# MICHAv41.net
KiCad netlist of a schematic drawn in EAGLE
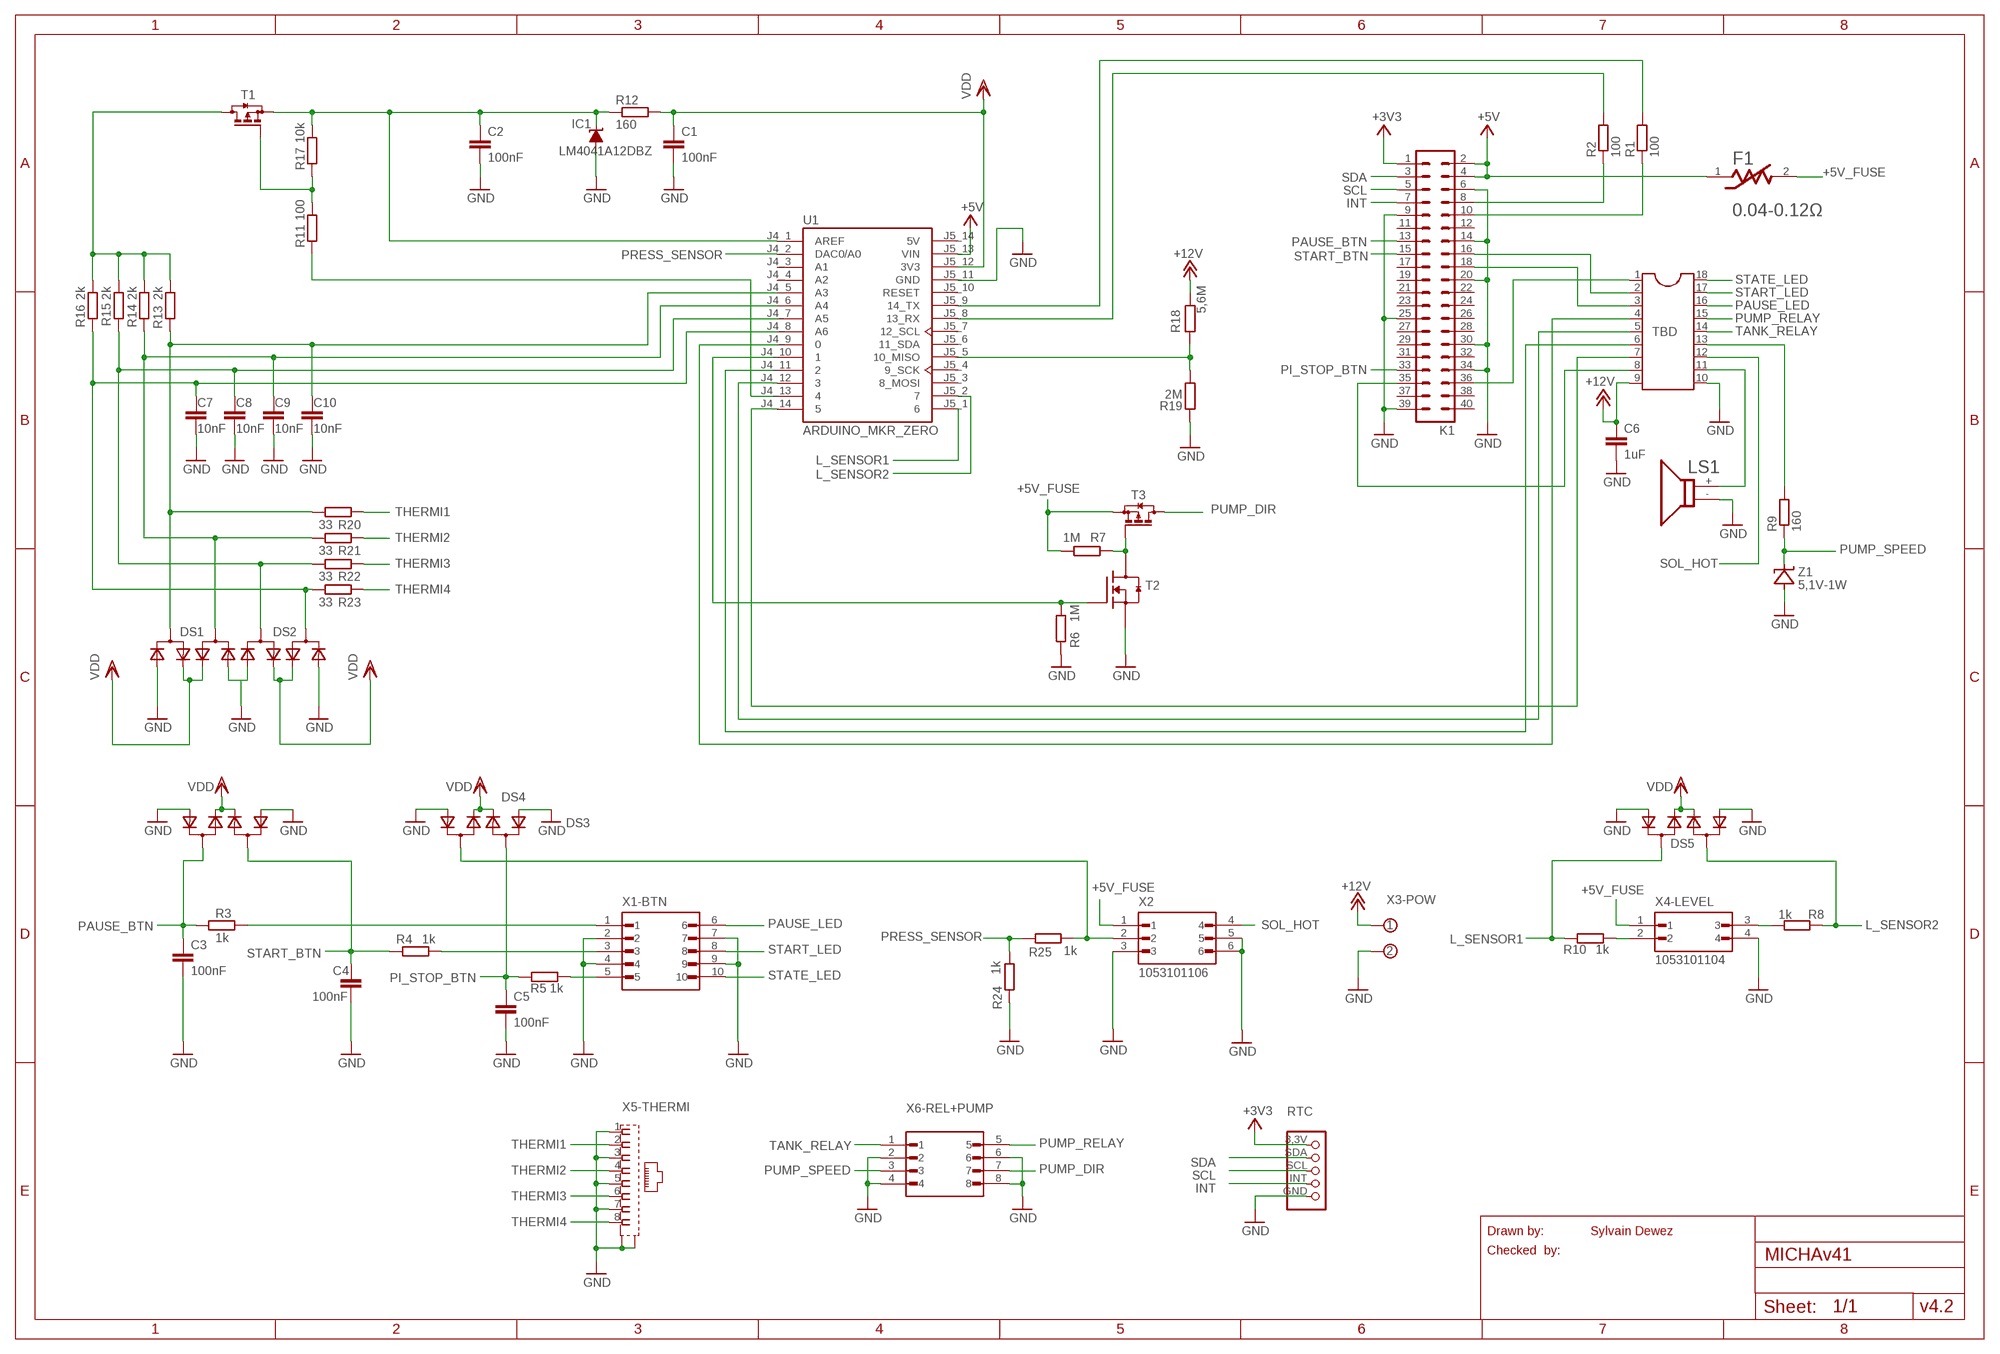
[diagram p0: schematic, sheet 1]

(export (version "E")
  (design (tool "Eeschema 10.0.6"))
  (components
    (comp (ref "C1")
      (value "100nF")
      (footprint "eagle-import:C1206")
      (libsource (lib "eagle-import") (part "C-EUC1206"))
    )
    (comp (ref "C2")
      (value "100nF")
      (footprint "eagle-import:C1206")
      (libsource (lib "eagle-import") (part "C-EUC1206"))
    )
    (comp (ref "C3")
      (value "100nF")
      (footprint "eagle-import:C1206")
      (libsource (lib "eagle-import") (part "C-EUC1206"))
    )
    (comp (ref "C4")
      (value "100nF")
      (footprint "eagle-import:C1206")
      (libsource (lib "eagle-import") (part "C-EUC1206"))
    )
    (comp (ref "C5")
      (value "100nF")
      (footprint "eagle-import:C1206")
      (libsource (lib "eagle-import") (part "C-EUC1206"))
    )
    (comp (ref "C6")
      (value "1uF")
      (footprint "eagle-import:C1206")
      (libsource (lib "eagle-import") (part "C-EUC1206"))
    )
    (comp (ref "C7")
      (value "10nF")
      (footprint "eagle-import:C1206")
      (libsource (lib "eagle-import") (part "C-EUC1206"))
    )
    (comp (ref "C8")
      (value "10nF")
      (footprint "eagle-import:C1206")
      (libsource (lib "eagle-import") (part "C-EUC1206"))
    )
    (comp (ref "C9")
      (value "10nF")
      (footprint "eagle-import:C1206")
      (libsource (lib "eagle-import") (part "C-EUC1206"))
    )
    (comp (ref "C10")
      (value "10nF")
      (footprint "eagle-import:C1206")
      (libsource (lib "eagle-import") (part "C-EUC1206"))
    )
    (comp (ref "DS1")
      (value "CMXSH2-4LSTRPBFREE")
      (footprint "eagle-import:CMXSH2-4LSTRPBFREE")
      (libsource (lib "eagle-import") (part "CMXSH2-4LSTRPBFREE"))
    )
    (comp (ref "DS2")
      (value "CMXSH2-4LSTRPBFREE")
      (footprint "eagle-import:CMXSH2-4LSTRPBFREE")
      (libsource (lib "eagle-import") (part "CMXSH2-4LSTRPBFREE"))
    )
    (comp (ref "DS3")
      (value "CMXSH2-4LSTRPBFREE")
      (footprint "eagle-import:CMXSH2-4LSTRPBFREE")
      (libsource (lib "eagle-import") (part "CMXSH2-4LSTRPBFREE"))
    )
    (comp (ref "DS4")
      (value "CMXSH2-4LSTRPBFREE")
      (footprint "eagle-import:CMXSH2-4LSTRPBFREE")
      (libsource (lib "eagle-import") (part "CMXSH2-4LSTRPBFREE"))
    )
    (comp (ref "DS5")
      (value "CMXSH2-4LSTRPBFREE")
      (footprint "eagle-import:CMXSH2-4LSTRPBFREE")
      (libsource (lib "eagle-import") (part "CMXSH2-4LSTRPBFREE"))
    )
    (comp (ref "F1")
      (value "LITTELFUSE_INC_1206L150THWRLITTELFUSE_INC_1206L150THWR_0_0")
      (footprint "eagle-import:LITTELFUSE_INC_1206L150THWR_0")
      (fields
        (field (name "DIGIKEY_PART_NUMBER") "F3372CT-ND")
        (field (name "MF") "Littelfuse Inc")
        (field (name "MOUSER_PART_NUMBER") "576-1206L150THWR")
      )
      (libsource (lib "eagle-import") (part "LITTELFUSE_INC_1206L150THWRLITTELFUSE_INC_1206L150THWR_0_0"))
    )
    (comp (ref "IC1")
      (value "LM4041A12DBZ")
      (footprint "eagle-import:DBZ_R-PDSO-G3")
      (fields (field (name "MPN") "LM4041A12IDBZR"))
      (libsource (lib "eagle-import") (part "LM4041DBZA12"))
    )
    (comp (ref "K1")
      (value "PIN20X2")
      (footprint "eagle-import:PIN_20X2")
      (libsource (lib "eagle-import") (part "PIN20X2"))
    )
    (comp (ref "LS1")
      (value "RSPRO-BUZZER-7800743")
      (footprint "eagle-import:RSPRO-BUZZER-7800743")
      (libsource (lib "eagle-import") (part "RSPRO-BUZZER-7800743"))
    )
    (comp (ref "R1")
      (value "100")
      (footprint "eagle-import:R1206")
      (libsource (lib "eagle-import") (part "resistor_R-EU_R1206"))
    )
    (comp (ref "R2")
      (value "100")
      (footprint "eagle-import:R1206")
      (libsource (lib "eagle-import") (part "resistor_R-EU_R1206"))
    )
    (comp (ref "R3")
      (value "1k")
      (footprint "eagle-import:R1206")
      (libsource (lib "eagle-import") (part "resistor_R-EU_R1206"))
    )
    (comp (ref "R4")
      (value "1k")
      (footprint "eagle-import:R1206")
      (libsource (lib "eagle-import") (part "resistor_R-EU_R1206"))
    )
    (comp (ref "R5")
      (value "1k")
      (footprint "eagle-import:R1206")
      (libsource (lib "eagle-import") (part "resistor_R-EU_R1206"))
    )
    (comp (ref "R6")
      (value "1M")
      (footprint "eagle-import:R1206")
      (libsource (lib "eagle-import") (part "resistor_R-EU_R1206"))
    )
    (comp (ref "R7")
      (value "1M")
      (footprint "eagle-import:R1206")
      (libsource (lib "eagle-import") (part "resistor_R-EU_R1206"))
    )
    (comp (ref "R8")
      (value "1k")
      (footprint "eagle-import:R1206")
      (libsource (lib "eagle-import") (part "resistor_R-EU_R1206"))
    )
    (comp (ref "R9")
      (value "160")
      (footprint "eagle-import:R1206")
      (libsource (lib "eagle-import") (part "R-EU_R1206"))
    )
    (comp (ref "R10")
      (value "1k")
      (footprint "eagle-import:R1206")
      (libsource (lib "eagle-import") (part "resistor_R-EU_R1206"))
    )
    (comp (ref "R11")
      (value "100")
      (footprint "eagle-import:R1206")
      (libsource (lib "eagle-import") (part "resistor_R-EU_R1206"))
    )
    (comp (ref "R12")
      (value "160")
      (footprint "eagle-import:R1206")
      (libsource (lib "eagle-import") (part "R-EU_R1206"))
    )
    (comp (ref "R13")
      (value "2k")
      (footprint "eagle-import:R1206")
      (libsource (lib "eagle-import") (part "resistor_R-EU_R1206"))
    )
    (comp (ref "R14")
      (value "2k")
      (footprint "eagle-import:R1206")
      (libsource (lib "eagle-import") (part "resistor_R-EU_R1206"))
    )
    (comp (ref "R15")
      (value "2k")
      (footprint "eagle-import:R1206")
      (libsource (lib "eagle-import") (part "resistor_R-EU_R1206"))
    )
    (comp (ref "R16")
      (value "2k")
      (footprint "eagle-import:R1206")
      (libsource (lib "eagle-import") (part "resistor_R-EU_R1206"))
    )
    (comp (ref "R17")
      (value "10k")
      (footprint "eagle-import:R1206")
      (libsource (lib "eagle-import") (part "resistor_R-EU_R1206"))
    )
    (comp (ref "R18")
      (value "5,6M")
      (footprint "eagle-import:R1206")
      (libsource (lib "eagle-import") (part "resistor_R-EU_R1206"))
    )
    (comp (ref "R19")
      (value "2M")
      (footprint "eagle-import:R1206")
      (libsource (lib "eagle-import") (part "resistor_R-EU_R1206"))
    )
    (comp (ref "R20")
      (value "33")
      (footprint "eagle-import:R1206")
      (libsource (lib "eagle-import") (part "resistor_R-EU_R1206"))
    )
    (comp (ref "R21")
      (value "33")
      (footprint "eagle-import:R1206")
      (libsource (lib "eagle-import") (part "resistor_R-EU_R1206"))
    )
    (comp (ref "R22")
      (value "33")
      (footprint "eagle-import:R1206")
      (libsource (lib "eagle-import") (part "resistor_R-EU_R1206"))
    )
    (comp (ref "R23")
      (value "33")
      (footprint "eagle-import:R1206")
      (libsource (lib "eagle-import") (part "resistor_R-EU_R1206"))
    )
    (comp (ref "R24")
      (value "1k")
      (footprint "eagle-import:R1206")
      (libsource (lib "eagle-import") (part "resistor_R-EU_R1206"))
    )
    (comp (ref "R25")
      (value "1k")
      (footprint "eagle-import:R1206")
      (libsource (lib "eagle-import") (part "resistor_R-EU_R1206"))
    )
    (comp (ref "RTC")
      (value "ODROID_C4_RTC_SHIELD")
      (footprint "eagle-import:ODROID_C4_RTC_SHIELD")
      (libsource (lib "eagle-import") (part "ODROID_C4_RTC_SHIELD"))
    )
    (comp (ref "T1")
      (value "BSS84")
      (footprint "eagle-import:SOT23")
      (libsource (lib "eagle-import") (part "BSS84"))
    )
    (comp (ref "T2")
      (value "MOSFET-NCH_SOT-23")
      (footprint "eagle-import:SOT95P280X135-3N")
      (libsource (lib "eagle-import") (part "MOSFET-NCH_SOT-23"))
    )
    (comp (ref "T3")
      (value "BSS84")
      (footprint "eagle-import:SOT23")
      (libsource (lib "eagle-import") (part "BSS84"))
    )
    (comp (ref "TBD")
      (value "DIL18S")
      (footprint "eagle-import:SOCKET-18")
      (libsource (lib "eagle-import") (part "DIL18S"))
    )
    (comp (ref "U1")
      (value "ARDUINO_MKR_ZERO")
      (footprint "eagle-import:MODULE_ARDUINO_MKR_ZERO")
      (fields (field (name "MF") "Arduino") (field (name "MP") "ARDUINO MKR ZERO"))
      (libsource (lib "eagle-import") (part "ARDUINO_MKR_ZERO"))
    )
    (comp (ref "X1-BTN")
      (value "1053101110")
      (footprint "eagle-import:MOLEX_1053101110")
      (fields (field (name "MANUFACTURER") "Molex"))
      (libsource (lib "eagle-import") (part "1053101110"))
    )
    (comp (ref "X2")
      (value "1053101106")
      (footprint "eagle-import:MOLEX_1053101106")
      (fields (field (name "MANUFACTURER") "Molex"))
      (libsource (lib "eagle-import") (part "1053101106"))
    )
    (comp (ref "X3-POW")
      (value "BUCHANAN_2_3.2MM")
      (footprint "eagle-import:BUCHANAN_2_3.5MM")
      (libsource (lib "eagle-import") (part "BUCHANAN_2_3.2MM"))
    )
    (comp (ref "X4-LEVEL")
      (value "1053101104")
      (footprint "eagle-import:MOLEX_1053101104")
      (fields (field (name "MANUFACTURER") "Molex"))
      (libsource (lib "eagle-import") (part "1053101104"))
    )
    (comp (ref "X5-THERMI")
      (value "SS-7188S-A-NF_V2")
      (footprint "eagle-import:BEL_SS-7188S-A-NF")
      (fields (field (name "MF") "Stewart Connector") (field (name "MP") "SS-7188S-A-NF"))
      (libsource (lib "eagle-import") (part "SS-7188S-A-NF_V2"))
    )
    (comp (ref "X6-REL+PUMP")
      (value "1053101108")
      (footprint "eagle-import:MOLEX_1053101108")
      (fields (field (name "MANUFACTURER") "Molex"))
      (libsource (lib "eagle-import") (part "1053101108"))
    )
    (comp (ref "Z1")
      (value "5,1V-1W")
      (footprint "eagle-import:ZENER_SMA")
      (libsource (lib "eagle-import") (part "ZENER_SMA"))
    )
  )
  (nets
    (net (code "1") (name "+3V3") (class "Default")
      (node (ref "K1") (pin "1") (pinfunction "1_1") (pintype "passive"))
      (node (ref "RTC") (pin "3,3V") (pinfunction "1_3,3V") (pintype "passive"))
    )
    (net (code "2") (name "+5V") (class "Default")
      (node (ref "F1") (pin "1") (pinfunction "1_1") (pintype "passive"))
      (node (ref "K1") (pin "2") (pinfunction "2_2") (pintype "passive"))
      (node (ref "K1") (pin "4") (pinfunction "4_4") (pintype "passive"))
      (node (ref "U1") (pin "J5_13") (pinfunction "VIN_J5_13") (pintype "power_in"))
    )
    (net (code "3") (name "+12V") (class "Default")
      (node (ref "C6") (pin "1") (pinfunction "1_1") (pintype "passive"))
      (node (ref "R18") (pin "2") (pinfunction "2_2") (pintype "passive"))
      (node (ref "TBD") (pin "9") (pinfunction "9_9") (pintype "passive"))
      (node (ref "X3-POW") (pin "1") (pinfunction "KL_1") (pintype "passive"))
    )
    (net (code "4") (name "/+5V_FUSE") (class "Default")
      (node (ref "F1") (pin "2") (pinfunction "2_2") (pintype "passive"))
      (node (ref "R7") (pin "2") (pinfunction "2_2") (pintype "passive"))
      (node (ref "T3") (pin "2") (pinfunction "S_2") (pintype "passive"))
      (node (ref "X2") (pin "1") (pinfunction "1_1") (pintype "passive"))
      (node (ref "X4-LEVEL") (pin "1") (pinfunction "1_1") (pintype "passive"))
    )
    (net (code "5") (name "/5V") (class "Default")
      (node (ref "U1") (pin "J5_14") (pinfunction "5V_J5_14") (pintype "power_in"))
    )
    (net (code "6") (name "/INT") (class "Default")
      (node (ref "K1") (pin "7") (pinfunction "7_7") (pintype "passive"))
      (node (ref "RTC") (pin "INT") (pinfunction "4_INT") (pintype "passive"))
    )
    (net (code "7") (name "/L_SENSOR1") (class "Default")
      (node (ref "DS5") (pin "5") (pinfunction "C_5") (pintype "passive"))
      (node (ref "R10") (pin "1") (pinfunction "1_1") (pintype "passive"))
      (node (ref "U1") (pin "J5_1") (pinfunction "6_J5_1") (pintype "bidirectional"))
    )
    (net (code "8") (name "/L_SENSOR2") (class "Default")
      (node (ref "DS5") (pin "2") (pinfunction "C1_2") (pintype "passive"))
      (node (ref "R8") (pin "1") (pinfunction "1_1") (pintype "passive"))
      (node (ref "U1") (pin "J5_2") (pinfunction "7_J5_2") (pintype "bidirectional"))
    )
    (net (code "9") (name "/PAUSE_BTN") (class "Default")
      (node (ref "C3") (pin "1") (pinfunction "1_1") (pintype "passive"))
      (node (ref "DS3") (pin "5") (pinfunction "C_5") (pintype "passive"))
      (node (ref "K1") (pin "13") (pinfunction "13_13") (pintype "passive"))
      (node (ref "R3") (pin "1") (pinfunction "1_1") (pintype "passive"))
    )
    (net (code "10") (name "/PAUSE_LED") (class "Default")
      (node (ref "TBD") (pin "16") (pinfunction "16_16") (pintype "passive"))
      (node (ref "X1-BTN") (pin "6") (pinfunction "6_6") (pintype "passive"))
    )
    (net (code "11") (name "/PI_STOP_BTN") (class "Default")
      (node (ref "C5") (pin "1") (pinfunction "1_1") (pintype "passive"))
      (node (ref "DS4") (pin "2") (pinfunction "C1_2") (pintype "passive"))
      (node (ref "K1") (pin "33") (pinfunction "33_33") (pintype "passive"))
      (node (ref "R5") (pin "1") (pinfunction "1_1") (pintype "passive"))
    )
    (net (code "12") (name "/PRESS_SENSOR") (class "Default")
      (node (ref "R24") (pin "2") (pinfunction "2_2") (pintype "passive"))
      (node (ref "R25") (pin "1") (pinfunction "1_1") (pintype "passive"))
      (node (ref "U1") (pin "J4_2") (pinfunction "DAC0/A0_J4_2") (pintype "bidirectional"))
    )
    (net (code "13") (name "/PUMP_DIR") (class "Default")
      (node (ref "T3") (pin "3") (pinfunction "D_3") (pintype "passive"))
      (node (ref "X6-REL+PUMP") (pin "7") (pinfunction "7_7") (pintype "passive"))
    )
    (net (code "14") (name "/PUMP_RELAY") (class "Default")
      (node (ref "TBD") (pin "15") (pinfunction "15_15") (pintype "passive"))
      (node (ref "X6-REL+PUMP") (pin "5") (pinfunction "5_5") (pintype "passive"))
    )
    (net (code "15") (name "/PUMP_SPEED") (class "Default")
      (node (ref "R9") (pin "1") (pinfunction "1_1") (pintype "passive"))
      (node (ref "X6-REL+PUMP") (pin "3") (pinfunction "3_3") (pintype "passive"))
      (node (ref "Z1") (pin "C") (pinfunction "C_C") (pintype "passive"))
    )
    (net (code "16") (name "/SCL") (class "Default")
      (node (ref "K1") (pin "5") (pinfunction "5_5") (pintype "passive"))
      (node (ref "RTC") (pin "SCL") (pinfunction "3_SCL") (pintype "passive"))
    )
    (net (code "17") (name "/SDA") (class "Default")
      (node (ref "K1") (pin "3") (pinfunction "3_3") (pintype "passive"))
      (node (ref "RTC") (pin "SDA") (pinfunction "2_SDA") (pintype "passive"))
    )
    (net (code "18") (name "/SOL_HOT") (class "Default")
      (node (ref "TBD") (pin "12") (pinfunction "12_12") (pintype "passive"))
      (node (ref "X2") (pin "4") (pinfunction "4_4") (pintype "passive"))
    )
    (net (code "19") (name "/START_BTN") (class "Default")
      (node (ref "C4") (pin "1") (pinfunction "1_1") (pintype "passive"))
      (node (ref "DS3") (pin "2") (pinfunction "C1_2") (pintype "passive"))
      (node (ref "K1") (pin "15") (pinfunction "15_15") (pintype "passive"))
      (node (ref "R4") (pin "1") (pinfunction "1_1") (pintype "passive"))
    )
    (net (code "20") (name "/START_LED") (class "Default")
      (node (ref "TBD") (pin "17") (pinfunction "17_17") (pintype "passive"))
      (node (ref "X1-BTN") (pin "8") (pinfunction "8_8") (pintype "passive"))
    )
    (net (code "21") (name "/STATE_LED") (class "Default")
      (node (ref "TBD") (pin "18") (pinfunction "18_18") (pintype "passive"))
      (node (ref "X1-BTN") (pin "10") (pinfunction "10_10") (pintype "passive"))
    )
    (net (code "22") (name "/TANK_RELAY") (class "Default")
      (node (ref "TBD") (pin "14") (pinfunction "14_14") (pintype "passive"))
      (node (ref "X6-REL+PUMP") (pin "1") (pinfunction "1_1") (pintype "passive"))
    )
    (net (code "23") (name "/THERMI1") (class "Default")
      (node (ref "R20") (pin "2") (pinfunction "2_2") (pintype "passive"))
      (node (ref "X5-THERMI") (pin "2") (pinfunction "2_2") (pintype "passive"))
    )
    (net (code "24") (name "/THERMI2") (class "Default")
      (node (ref "R21") (pin "2") (pinfunction "2_2") (pintype "passive"))
      (node (ref "X5-THERMI") (pin "4") (pinfunction "4_4") (pintype "passive"))
    )
    (net (code "25") (name "/THERMI3") (class "Default")
      (node (ref "R22") (pin "2") (pinfunction "2_2") (pintype "passive"))
      (node (ref "X5-THERMI") (pin "6") (pinfunction "6_6") (pintype "passive"))
    )
    (net (code "26") (name "/THERMI4") (class "Default")
      (node (ref "R23") (pin "2") (pinfunction "2_2") (pintype "passive"))
      (node (ref "X5-THERMI") (pin "8") (pinfunction "8_8") (pintype "passive"))
    )
    (net (code "27") (name "GND") (class "Default")
      (node (ref "C1") (pin "2") (pinfunction "2_2") (pintype "passive"))
      (node (ref "C10") (pin "2") (pinfunction "2_2") (pintype "passive"))
      (node (ref "C2") (pin "2") (pinfunction "2_2") (pintype "passive"))
      (node (ref "C3") (pin "2") (pinfunction "2_2") (pintype "passive"))
      (node (ref "C4") (pin "2") (pinfunction "2_2") (pintype "passive"))
      (node (ref "C5") (pin "2") (pinfunction "2_2") (pintype "passive"))
      (node (ref "C6") (pin "2") (pinfunction "2_2") (pintype "passive"))
      (node (ref "C7") (pin "2") (pinfunction "2_2") (pintype "passive"))
      (node (ref "C8") (pin "2") (pinfunction "2_2") (pintype "passive"))
      (node (ref "C9") (pin "2") (pinfunction "2_2") (pintype "passive"))
      (node (ref "DS1") (pin "1") (pinfunction "A3_1") (pintype "passive"))
      (node (ref "DS1") (pin "6") (pinfunction "A2_6") (pintype "passive"))
      (node (ref "DS2") (pin "1") (pinfunction "A3_1") (pintype "passive"))
      (node (ref "DS2") (pin "6") (pinfunction "A2_6") (pintype "passive"))
      (node (ref "DS3") (pin "1") (pinfunction "A3_1") (pintype "passive"))
      (node (ref "DS3") (pin "6") (pinfunction "A2_6") (pintype "passive"))
      (node (ref "DS4") (pin "1") (pinfunction "A3_1") (pintype "passive"))
      (node (ref "DS4") (pin "6") (pinfunction "A2_6") (pintype "passive"))
      (node (ref "DS5") (pin "1") (pinfunction "A3_1") (pintype "passive"))
      (node (ref "DS5") (pin "6") (pinfunction "A2_6") (pintype "passive"))
      (node (ref "IC1") (pin "2") (pinfunction "A_2") (pintype "passive"))
      (node (ref "K1") (pin "14") (pinfunction "14_14") (pintype "passive"))
      (node (ref "K1") (pin "20") (pinfunction "20_20") (pintype "passive"))
      (node (ref "K1") (pin "25") (pinfunction "25_25") (pintype "passive"))
      (node (ref "K1") (pin "30") (pinfunction "30_30") (pintype "passive"))
      (node (ref "K1") (pin "34") (pinfunction "34_34") (pintype "passive"))
      (node (ref "K1") (pin "39") (pinfunction "39_39") (pintype "passive"))
      (node (ref "K1") (pin "6") (pinfunction "6_6") (pintype "passive"))
      (node (ref "K1") (pin "9") (pinfunction "9_9") (pintype "passive"))
      (node (ref "LS1") (pin "-") (pinfunction "2_-") (pintype "passive"))
      (node (ref "R19") (pin "1") (pinfunction "1_1") (pintype "passive"))
      (node (ref "R24") (pin "1") (pinfunction "1_1") (pintype "passive"))
      (node (ref "R6") (pin "1") (pinfunction "1_1") (pintype "passive"))
      (node (ref "RTC") (pin "GND") (pinfunction "5_GND") (pintype "passive"))
      (node (ref "T2") (pin "2") (pinfunction "S_2") (pintype "passive"))
      (node (ref "TBD") (pin "10") (pinfunction "10_10") (pintype "passive"))
      (node (ref "U1") (pin "J5_11") (pinfunction "GND_J5_11") (pintype "power_in"))
      (node (ref "X1-BTN") (pin "2") (pinfunction "2_2") (pintype "passive"))
      (node (ref "X1-BTN") (pin "4") (pinfunction "4_4") (pintype "passive"))
      (node (ref "X1-BTN") (pin "7") (pinfunction "7_7") (pintype "passive"))
      (node (ref "X1-BTN") (pin "9") (pinfunction "9_9") (pintype "passive"))
      (node (ref "X2") (pin "3") (pinfunction "3_3") (pintype "passive"))
      (node (ref "X2") (pin "5") (pinfunction "5_5") (pintype "passive"))
      (node (ref "X2") (pin "6") (pinfunction "6_6") (pintype "passive"))
      (node (ref "X3-POW") (pin "2") (pinfunction "KL1_2") (pintype "passive"))
      (node (ref "X4-LEVEL") (pin "4") (pinfunction "4_4") (pintype "passive"))
      (node (ref "X5-THERMI") (pin "1") (pinfunction "1_1") (pintype "passive"))
      (node (ref "X5-THERMI") (pin "3") (pinfunction "3_3") (pintype "passive"))
      (node (ref "X5-THERMI") (pin "5") (pinfunction "5_5") (pintype "passive"))
      (node (ref "X5-THERMI") (pin "7") (pinfunction "7_7") (pintype "passive"))
      (node (ref "X5-THERMI") (pin "S1") (pinfunction "GND1_S1") (pintype "passive"))
      (node (ref "X5-THERMI") (pin "S2") (pinfunction "GND2_S2") (pintype "passive"))
      (node (ref "X6-REL+PUMP") (pin "2") (pinfunction "2_2") (pintype "passive"))
      (node (ref "X6-REL+PUMP") (pin "4") (pinfunction "4_4") (pintype "passive"))
      (node (ref "X6-REL+PUMP") (pin "6") (pinfunction "6_6") (pintype "passive"))
      (node (ref "X6-REL+PUMP") (pin "8") (pinfunction "8_8") (pintype "passive"))
      (node (ref "Z1") (pin "A") (pinfunction "A_A") (pintype "passive"))
    )
    (net (code "28") (name "Net-(DS1-C)") (class "Default")
      (node (ref "C9") (pin "1") (pinfunction "1_1") (pintype "passive"))
      (node (ref "DS1") (pin "5") (pinfunction "C_5") (pintype "passive"))
      (node (ref "R14") (pin "2") (pinfunction "2_2") (pintype "passive"))
      (node (ref "R21") (pin "1") (pinfunction "1_1") (pintype "passive"))
      (node (ref "U1") (pin "J4_6") (pinfunction "A4_J4_6") (pintype "bidirectional"))
    )
    (net (code "29") (name "Net-(DS1-C1)") (class "Default")
      (node (ref "C10") (pin "1") (pinfunction "1_1") (pintype "passive"))
      (node (ref "DS1") (pin "2") (pinfunction "C1_2") (pintype "passive"))
      (node (ref "R13") (pin "2") (pinfunction "2_2") (pintype "passive"))
      (node (ref "R20") (pin "1") (pinfunction "1_1") (pintype "passive"))
      (node (ref "U1") (pin "J4_5") (pinfunction "A3_J4_5") (pintype "bidirectional"))
    )
    (net (code "30") (name "Net-(DS2-C)") (class "Default")
      (node (ref "C7") (pin "1") (pinfunction "1_1") (pintype "passive"))
      (node (ref "DS2") (pin "5") (pinfunction "C_5") (pintype "passive"))
      (node (ref "R16") (pin "2") (pinfunction "2_2") (pintype "passive"))
      (node (ref "R23") (pin "1") (pinfunction "1_1") (pintype "passive"))
      (node (ref "U1") (pin "J4_8") (pinfunction "A6_J4_8") (pintype "bidirectional"))
    )
    (net (code "31") (name "Net-(DS2-C1)") (class "Default")
      (node (ref "C8") (pin "1") (pinfunction "1_1") (pintype "passive"))
      (node (ref "DS2") (pin "2") (pinfunction "C1_2") (pintype "passive"))
      (node (ref "R15") (pin "2") (pinfunction "2_2") (pintype "passive"))
      (node (ref "R22") (pin "1") (pinfunction "1_1") (pintype "passive"))
      (node (ref "U1") (pin "J4_7") (pinfunction "A5_J4_7") (pintype "bidirectional"))
    )
    (net (code "32") (name "Net-(DS4-C)") (class "Default")
      (node (ref "DS4") (pin "5") (pinfunction "C_5") (pintype "passive"))
      (node (ref "R25") (pin "2") (pinfunction "2_2") (pintype "passive"))
      (node (ref "X2") (pin "2") (pinfunction "2_2") (pintype "passive"))
    )
    (net (code "33") (name "Net-(IC1-C)") (class "Default")
      (node (ref "C2") (pin "1") (pinfunction "1_1") (pintype "passive"))
      (node (ref "IC1") (pin "1") (pinfunction "C_1") (pintype "passive"))
      (node (ref "R12") (pin "1") (pinfunction "1_1") (pintype "passive"))
      (node (ref "R17") (pin "2") (pinfunction "2_2") (pintype "passive"))
      (node (ref "T1") (pin "2") (pinfunction "S_2") (pintype "passive"))
      (node (ref "U1") (pin "J4_1") (pinfunction "AREF_J4_1") (pintype "bidirectional"))
    )
    (net (code "34") (name "Net-(K1-Pad8)") (class "Default")
      (node (ref "K1") (pin "8") (pinfunction "8_8") (pintype "passive"))
      (node (ref "R2") (pin "1") (pinfunction "1_1") (pintype "passive"))
    )
    (net (code "35") (name "Net-(K1-Pad10)") (class "Default")
      (node (ref "K1") (pin "10") (pinfunction "10_10") (pintype "passive"))
      (node (ref "R1") (pin "1") (pinfunction "1_1") (pintype "passive"))
    )
    (net (code "36") (name "Net-(K1-Pad16)") (class "Default")
      (node (ref "K1") (pin "16") (pinfunction "16_16") (pintype "passive"))
      (node (ref "TBD") (pin "2") (pinfunction "2_2") (pintype "passive"))
    )
    (net (code "37") (name "Net-(K1-Pad18)") (class "Default")
      (node (ref "K1") (pin "18") (pinfunction "18_18") (pintype "passive"))
      (node (ref "TBD") (pin "3") (pinfunction "3_3") (pintype "passive"))
    )
    (net (code "38") (name "Net-(K1-Pad35)") (class "Default")
      (node (ref "K1") (pin "35") (pinfunction "35_35") (pintype "passive"))
      (node (ref "TBD") (pin "8") (pinfunction "8_8") (pintype "passive"))
    )
    (net (code "39") (name "Net-(K1-Pad36)") (class "Default")
      (node (ref "K1") (pin "36") (pinfunction "36_36") (pintype "passive"))
      (node (ref "TBD") (pin "1") (pinfunction "1_1") (pintype "passive"))
    )
    (net (code "40") (name "Net-(LS1-1)") (class "Default")
      (node (ref "LS1") (pin "+") (pinfunction "1_+") (pintype "passive"))
      (node (ref "TBD") (pin "11") (pinfunction "11_11") (pintype "passive"))
    )
    (net (code "41") (name "Net-(R3-Pad2)") (class "Default")
      (node (ref "R3") (pin "2") (pinfunction "2_2") (pintype "passive"))
      (node (ref "X1-BTN") (pin "1") (pinfunction "1_1") (pintype "passive"))
    )
    (net (code "42") (name "Net-(R4-Pad2)") (class "Default")
      (node (ref "R4") (pin "2") (pinfunction "2_2") (pintype "passive"))
      (node (ref "X1-BTN") (pin "3") (pinfunction "3_3") (pintype "passive"))
    )
    (net (code "43") (name "Net-(R5-Pad2)") (class "Default")
      (node (ref "R5") (pin "2") (pinfunction "2_2") (pintype "passive"))
      (node (ref "X1-BTN") (pin "5") (pinfunction "5_5") (pintype "passive"))
    )
    (net (code "44") (name "Net-(R8-Pad2)") (class "Default")
      (node (ref "R8") (pin "2") (pinfunction "2_2") (pintype "passive"))
      (node (ref "X4-LEVEL") (pin "3") (pinfunction "3_3") (pintype "passive"))
    )
    (net (code "45") (name "Net-(R9-Pad2)") (class "Default")
      (node (ref "R9") (pin "2") (pinfunction "2_2") (pintype "passive"))
      (node (ref "TBD") (pin "13") (pinfunction "13_13") (pintype "passive"))
    )
    (net (code "46") (name "Net-(R10-Pad2)") (class "Default")
      (node (ref "R10") (pin "2") (pinfunction "2_2") (pintype "passive"))
      (node (ref "X4-LEVEL") (pin "2") (pinfunction "2_2") (pintype "passive"))
    )
    (net (code "47") (name "Net-(T1-D)") (class "Default")
      (node (ref "R13") (pin "1") (pinfunction "1_1") (pintype "passive"))
      (node (ref "R14") (pin "1") (pinfunction "1_1") (pintype "passive"))
      (node (ref "R15") (pin "1") (pinfunction "1_1") (pintype "passive"))
      (node (ref "R16") (pin "1") (pinfunction "1_1") (pintype "passive"))
      (node (ref "T1") (pin "3") (pinfunction "D_3") (pintype "passive"))
    )
    (net (code "48") (name "Net-(T1-G)") (class "Default")
      (node (ref "R11") (pin "2") (pinfunction "2_2") (pintype "passive"))
      (node (ref "R17") (pin "1") (pinfunction "1_1") (pintype "passive"))
      (node (ref "T1") (pin "1") (pinfunction "G_1") (pintype "passive"))
    )
    (net (code "49") (name "Net-(T2-D)") (class "Default")
      (node (ref "R7") (pin "1") (pinfunction "1_1") (pintype "passive"))
      (node (ref "T2") (pin "3") (pinfunction "D_3") (pintype "passive"))
      (node (ref "T3") (pin "1") (pinfunction "G_1") (pintype "passive"))
    )
    (net (code "50") (name "Net-(T2-G)") (class "Default")
      (node (ref "R6") (pin "2") (pinfunction "2_2") (pintype "passive"))
      (node (ref "T2") (pin "1") (pinfunction "G_1") (pintype "passive"))
      (node (ref "U1") (pin "J4_10") (pinfunction "1_J4_10") (pintype "bidirectional"))
    )
    (net (code "51") (name "Net-(U1-0)") (class "Default")
      (node (ref "TBD") (pin "4") (pinfunction "4_4") (pintype "passive"))
      (node (ref "U1") (pin "J4_9") (pinfunction "0_J4_9") (pintype "bidirectional"))
    )
    (net (code "52") (name "Net-(U1-2)") (class "Default")
      (node (ref "TBD") (pin "6") (pinfunction "6_6") (pintype "passive"))
      (node (ref "U1") (pin "J4_11") (pinfunction "2_J4_11") (pintype "bidirectional"))
    )
    (net (code "53") (name "Net-(U1-3)") (class "Default")
      (node (ref "TBD") (pin "5") (pinfunction "5_5") (pintype "passive"))
      (node (ref "U1") (pin "J4_12") (pinfunction "3_J4_12") (pintype "bidirectional"))
    )
    (net (code "54") (name "Net-(U1-4)") (class "Default")
      (node (ref "R11") (pin "1") (pinfunction "1_1") (pintype "passive"))
      (node (ref "U1") (pin "J4_13") (pinfunction "4_J4_13") (pintype "bidirectional"))
    )
    (net (code "55") (name "Net-(U1-5)") (class "Default")
      (node (ref "TBD") (pin "7") (pinfunction "7_7") (pintype "passive"))
      (node (ref "U1") (pin "J4_14") (pinfunction "5_J4_14") (pintype "bidirectional"))
    )
    (net (code "56") (name "Net-(U1-10_MISO)") (class "Default")
      (node (ref "R18") (pin "1") (pinfunction "1_1") (pintype "passive"))
      (node (ref "R19") (pin "2") (pinfunction "2_2") (pintype "passive"))
      (node (ref "U1") (pin "J5_5") (pinfunction "10_MISO_J5_5") (pintype "bidirectional"))
    )
    (net (code "57") (name "Net-(U1-13_RX)") (class "Default")
      (node (ref "R2") (pin "2") (pinfunction "2_2") (pintype "passive"))
      (node (ref "U1") (pin "J5_8") (pinfunction "13_RX_J5_8") (pintype "input"))
    )
    (net (code "58") (name "Net-(U1-14_TX)") (class "Default")
      (node (ref "R1") (pin "2") (pinfunction "2_2") (pintype "passive"))
      (node (ref "U1") (pin "J5_9") (pinfunction "14_TX_J5_9") (pintype "output"))
    )
    (net (code "59") (name "VDD") (class "Default")
      (node (ref "C1") (pin "1") (pinfunction "1_1") (pintype "passive"))
      (node (ref "DS1") (pin "3") (pinfunction "A4_3") (pintype "passive"))
      (node (ref "DS1") (pin "4") (pinfunction "A1_4") (pintype "passive"))
      (node (ref "DS2") (pin "3") (pinfunction "A4_3") (pintype "passive"))
      (node (ref "DS2") (pin "4") (pinfunction "A1_4") (pintype "passive"))
      (node (ref "DS3") (pin "3") (pinfunction "A4_3") (pintype "passive"))
      (node (ref "DS3") (pin "4") (pinfunction "A1_4") (pintype "passive"))
      (node (ref "DS4") (pin "3") (pinfunction "A4_3") (pintype "passive"))
      (node (ref "DS4") (pin "4") (pinfunction "A1_4") (pintype "passive"))
      (node (ref "DS5") (pin "3") (pinfunction "A4_3") (pintype "passive"))
      (node (ref "DS5") (pin "4") (pinfunction "A1_4") (pintype "passive"))
      (node (ref "R12") (pin "2") (pinfunction "2_2") (pintype "passive"))
      (node (ref "U1") (pin "J5_12") (pinfunction "3V3_J5_12") (pintype "power_in"))
    )
    (net (code "60") (name "unconnected-(K1-Pad11)") (class "Default")
      (node (ref "K1") (pin "11") (pinfunction "11_11") (pintype "passive"))
    )
    (net (code "61") (name "unconnected-(K1-Pad12)") (class "Default")
      (node (ref "K1") (pin "12") (pinfunction "12_12") (pintype "passive"))
    )
    (net (code "62") (name "unconnected-(K1-Pad17)") (class "Default")
      (node (ref "K1") (pin "17") (pinfunction "17_17") (pintype "passive"))
    )
    (net (code "63") (name "unconnected-(K1-Pad19)") (class "Default")
      (node (ref "K1") (pin "19") (pinfunction "19_19") (pintype "passive"))
    )
    (net (code "64") (name "unconnected-(K1-Pad21)") (class "Default")
      (node (ref "K1") (pin "21") (pinfunction "21_21") (pintype "passive"))
    )
    (net (code "65") (name "unconnected-(K1-Pad22)") (class "Default")
      (node (ref "K1") (pin "22") (pinfunction "22_22") (pintype "passive"))
    )
    (net (code "66") (name "unconnected-(K1-Pad23)") (class "Default")
      (node (ref "K1") (pin "23") (pinfunction "23_23") (pintype "passive"))
    )
    (net (code "67") (name "unconnected-(K1-Pad24)") (class "Default")
      (node (ref "K1") (pin "24") (pinfunction "24_24") (pintype "passive"))
    )
    (net (code "68") (name "unconnected-(K1-Pad26)") (class "Default")
      (node (ref "K1") (pin "26") (pinfunction "26_26") (pintype "passive"))
    )
    (net (code "69") (name "unconnected-(K1-Pad27)") (class "Default")
      (node (ref "K1") (pin "27") (pinfunction "27_27") (pintype "passive"))
    )
    (net (code "70") (name "unconnected-(K1-Pad28)") (class "Default")
      (node (ref "K1") (pin "28") (pinfunction "28_28") (pintype "passive"))
    )
    (net (code "71") (name "unconnected-(K1-Pad29)") (class "Default")
      (node (ref "K1") (pin "29") (pinfunction "29_29") (pintype "passive"))
    )
    (net (code "72") (name "unconnected-(K1-Pad31)") (class "Default")
      (node (ref "K1") (pin "31") (pinfunction "31_31") (pintype "passive"))
    )
    (net (code "73") (name "unconnected-(K1-Pad32)") (class "Default")
      (node (ref "K1") (pin "32") (pinfunction "32_32") (pintype "passive"))
    )
    (net (code "74") (name "unconnected-(K1-Pad37)") (class "Default")
      (node (ref "K1") (pin "37") (pinfunction "37_37") (pintype "passive"))
    )
    (net (code "75") (name "unconnected-(K1-Pad38)") (class "Default")
      (node (ref "K1") (pin "38") (pinfunction "38_38") (pintype "passive"))
    )
    (net (code "76") (name "unconnected-(K1-Pad40)") (class "Default")
      (node (ref "K1") (pin "40") (pinfunction "40_40") (pintype "passive"))
    )
    (net (code "77") (name "unconnected-(U1-8_MOSI-PadJ5_3)") (class "Default")
      (node (ref "U1") (pin "J5_3") (pinfunction "8_MOSI_J5_3") (pintype "bidirectional"))
    )
    (net (code "78") (name "unconnected-(U1-9_SCK-PadJ5_4)") (class "Default")
      (node (ref "U1") (pin "J5_4") (pinfunction "9_SCK_J5_4") (pintype "bidirectional"))
    )
    (net (code "79") (name "unconnected-(U1-11_SDA-PadJ5_6)") (class "Default")
      (node (ref "U1") (pin "J5_6") (pinfunction "11_SDA_J5_6") (pintype "bidirectional"))
    )
    (net (code "80") (name "unconnected-(U1-12_SCL-PadJ5_7)") (class "Default")
      (node (ref "U1") (pin "J5_7") (pinfunction "12_SCL_J5_7") (pintype "bidirectional"))
    )
    (net (code "81") (name "unconnected-(U1-A1-PadJ4_3)") (class "Default")
      (node (ref "U1") (pin "J4_3") (pinfunction "A1_J4_3") (pintype "bidirectional"))
    )
    (net (code "82") (name "unconnected-(U1-A2-PadJ4_4)") (class "Default")
      (node (ref "U1") (pin "J4_4") (pinfunction "A2_J4_4") (pintype "bidirectional"))
    )
    (net (code "83") (name "unconnected-(U1-RESET-PadJ5_10)") (class "Default")
      (node (ref "U1") (pin "J5_10") (pinfunction "RESET_J5_10") (pintype "bidirectional"))
    )
  )
)
